# TCS3472_breakout.net
KiCad netlist of a schematic drawn in EAGLE
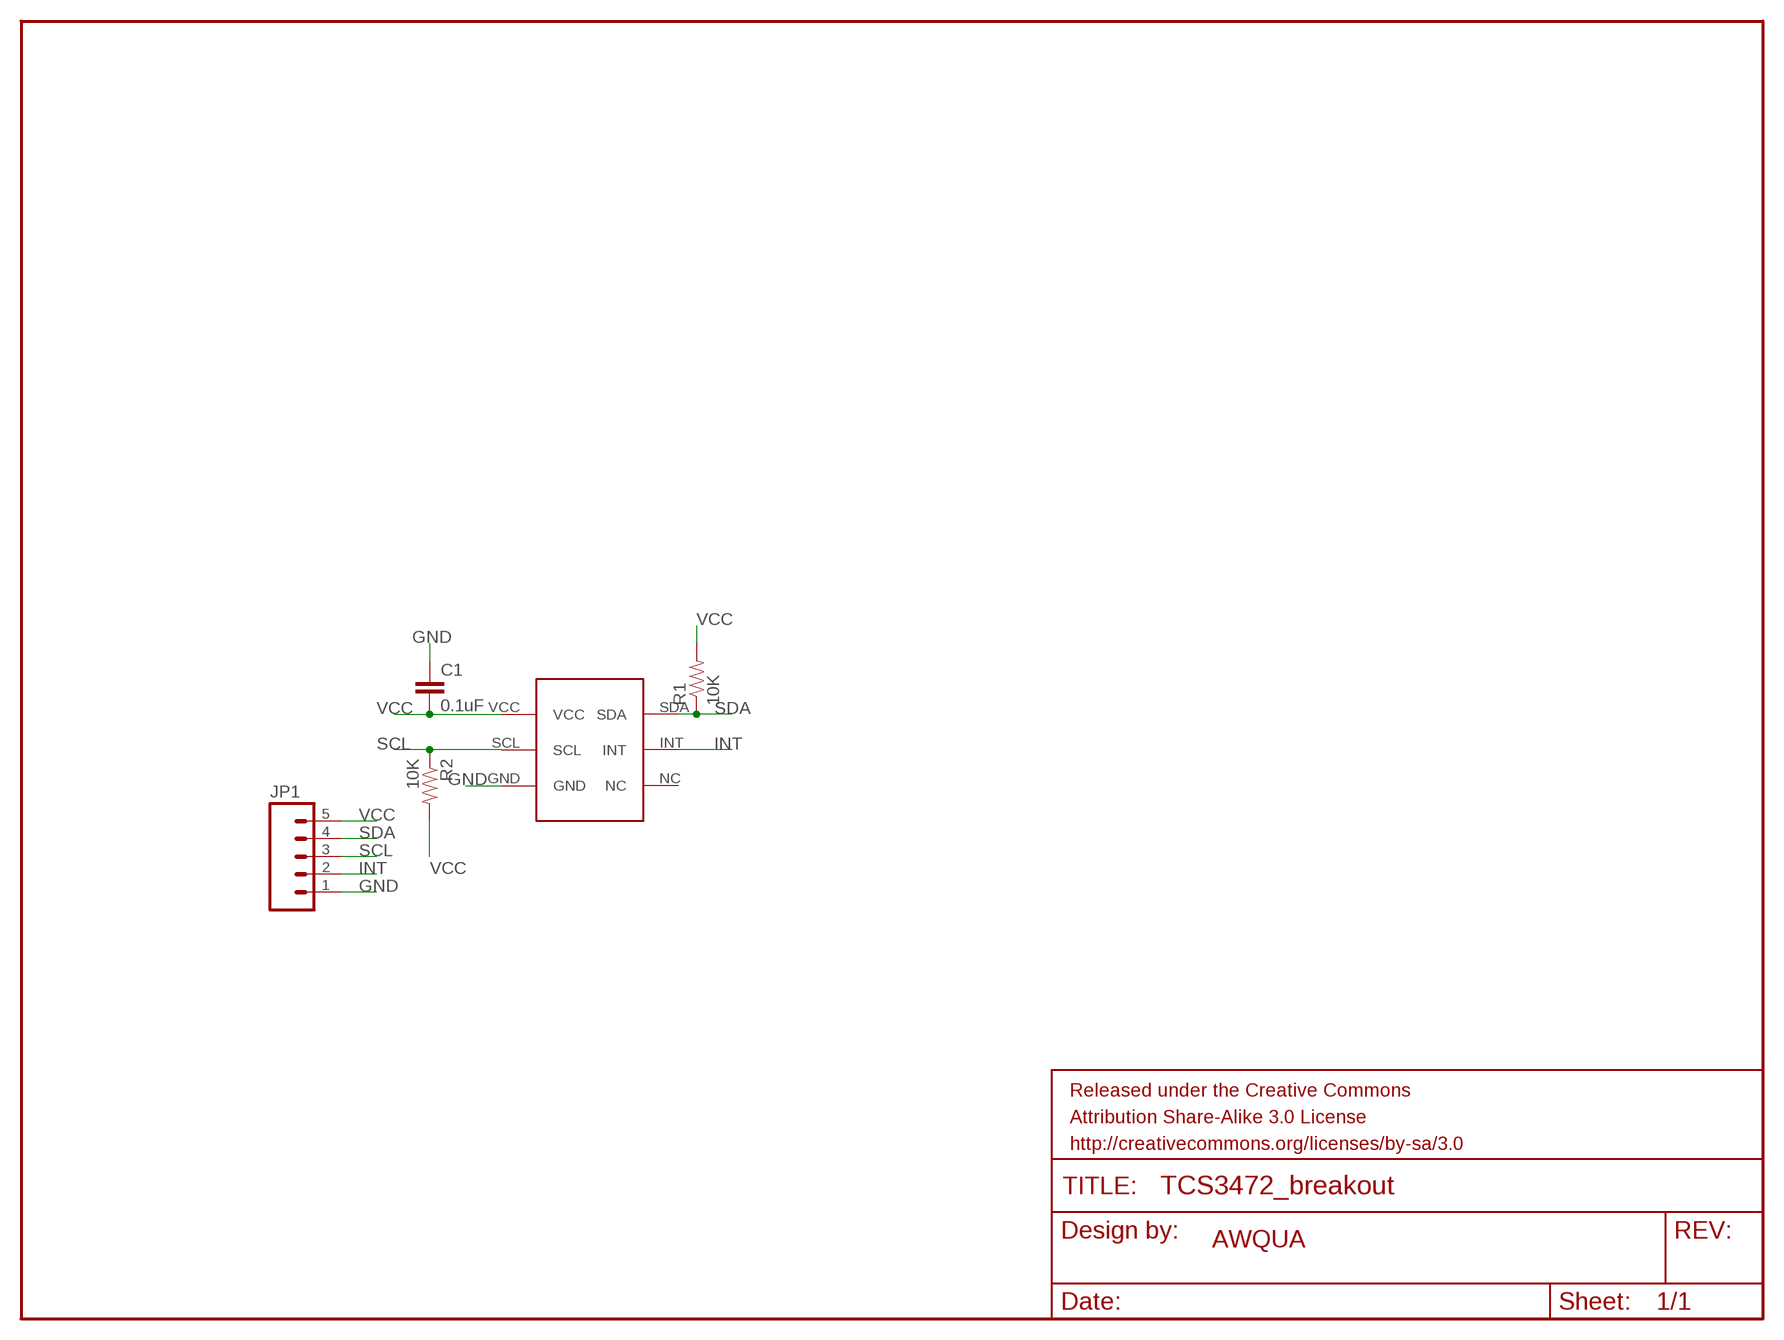
[diagram p0: schematic, sheet 1]

(export (version "E")
  (design (tool "Eeschema 10.0.6"))
  (components
    (comp (ref "C1")
      (value "0.1uF")
      (footprint "eagle-import:0603-CAP")
      (libsource (lib "eagle-import") (part "CAP0603-CAP"))
    )
    (comp (ref "FRAME1")
      (value "FRAME-LETTER")
      (footprint "eagle-import:CREATIVE_COMMONS")
      (libsource (lib "eagle-import") (part "FRAME-LETTER"))
    )
    (comp (ref "JP1")
      (value "M05NO_SILK")
      (footprint "eagle-import:1X05_NO_SILK")
      (libsource (lib "eagle-import") (part "M05NO_SILK"))
    )
    (comp (ref "R1")
      (value "10K")
      (footprint "eagle-import:0603-RES")
      (libsource (lib "eagle-import") (part "RESISTOR0603-RES"))
    )
    (comp (ref "R2")
      (value "10K")
      (footprint "eagle-import:0603-RES")
      (libsource (lib "eagle-import") (part "RESISTOR0603-RES"))
    )
    (comp (ref "U$2")
      (value "TCS3472")
      (footprint "eagle-import:TCS3472")
      (libsource (lib "eagle-import") (part "TCS3472"))
    )
  )
  (nets
    (net (code "1") (name "/GND") (class "Default")
      (node (ref "C1") (pin "1") (pinfunction "1_1") (pintype "passive"))
      (node (ref "JP1") (pin "1") (pinfunction "1_1") (pintype "passive"))
      (node (ref "U$2") (pin "GND") (pinfunction "GND_GND") (pintype "bidirectional"))
    )
    (net (code "2") (name "/INT") (class "Default")
      (node (ref "JP1") (pin "2") (pinfunction "2_2") (pintype "passive"))
      (node (ref "U$2") (pin "INT") (pinfunction "INT_INT") (pintype "bidirectional"))
    )
    (net (code "3") (name "/SCL") (class "Default")
      (node (ref "JP1") (pin "3") (pinfunction "3_3") (pintype "passive"))
      (node (ref "R2") (pin "1") (pinfunction "1_1") (pintype "passive"))
      (node (ref "U$2") (pin "SCL") (pinfunction "SCL_SCL") (pintype "bidirectional"))
    )
    (net (code "4") (name "/SDA") (class "Default")
      (node (ref "JP1") (pin "4") (pinfunction "4_4") (pintype "passive"))
      (node (ref "R1") (pin "1") (pinfunction "1_1") (pintype "passive"))
      (node (ref "U$2") (pin "SDA") (pinfunction "SDA_SDA") (pintype "bidirectional"))
    )
    (net (code "5") (name "/VCC") (class "Default")
      (node (ref "C1") (pin "2") (pinfunction "2_2") (pintype "passive"))
      (node (ref "JP1") (pin "5") (pinfunction "5_5") (pintype "passive"))
      (node (ref "R1") (pin "2") (pinfunction "2_2") (pintype "passive"))
      (node (ref "R2") (pin "2") (pinfunction "2_2") (pintype "passive"))
      (node (ref "U$2") (pin "VCC") (pinfunction "VCC_VCC") (pintype "bidirectional"))
    )
    (net (code "6") (name "unconnected-(U$2-PadNC)") (class "Default")
      (node (ref "U$2") (pin "NC") (pinfunction "NC_NC") (pintype "bidirectional"))
    )
  )
)
